# MCU.net
KiCad netlist of a schematic drawn in Altium Designer
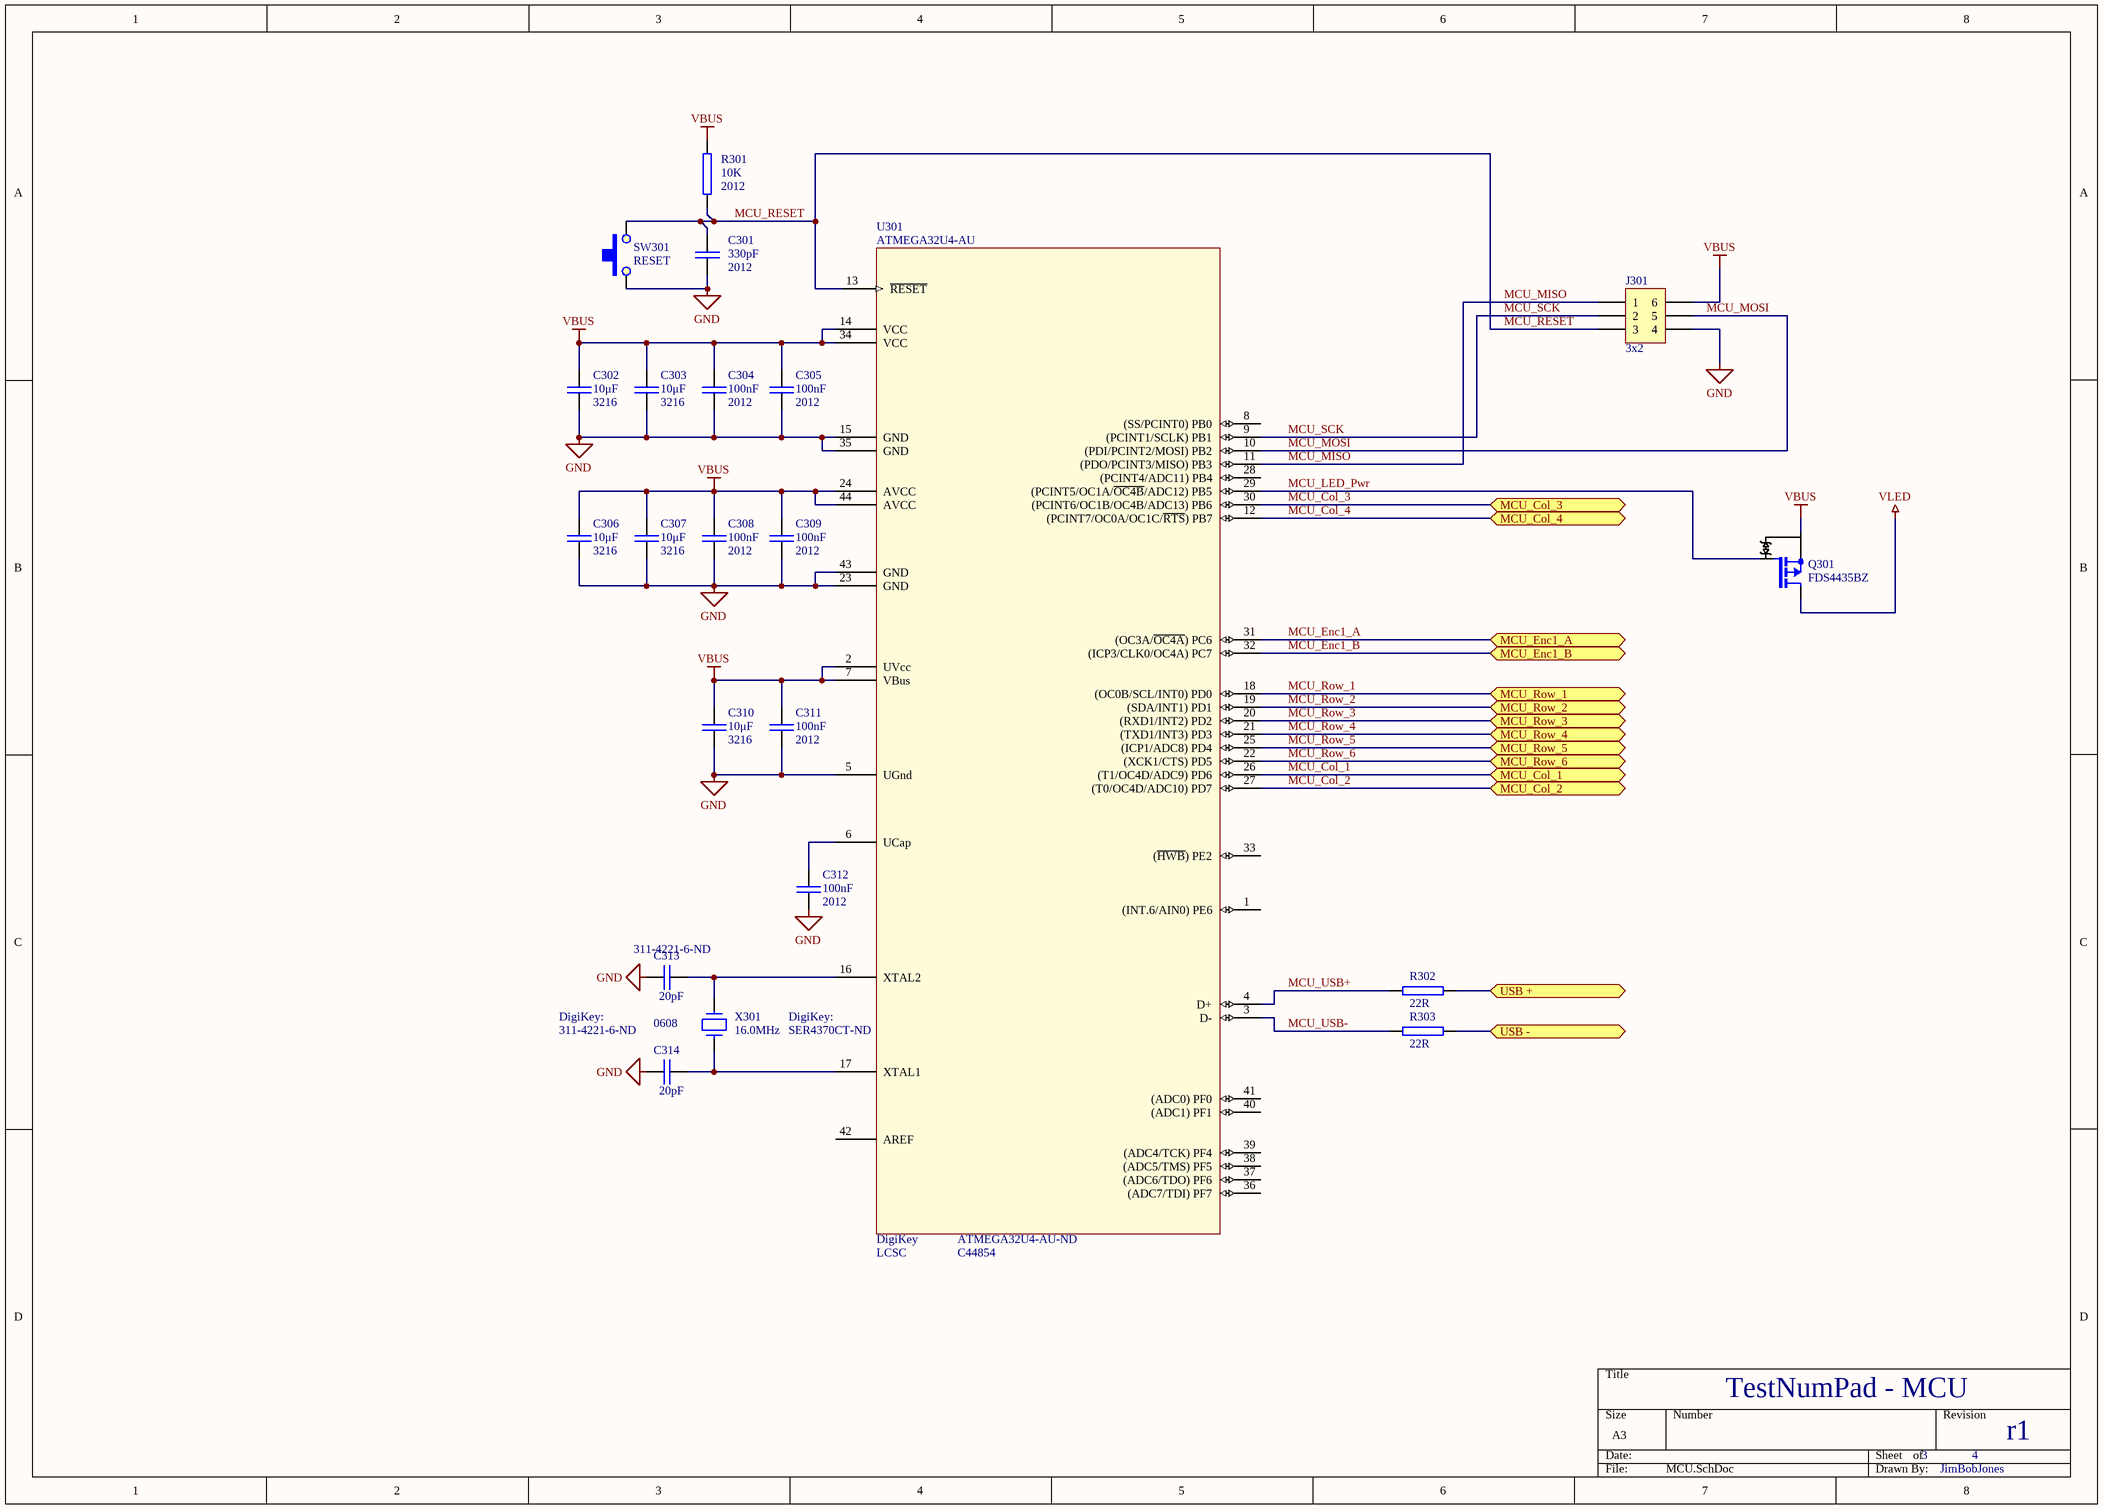
[diagram p0: MCU.SchDoc]

(export (version "E")
  (design (tool "Eeschema 10.0.6"))
  (components
    (comp (ref "C301")
      (value "330pF")
      (footprint "2012C (0805)")
      (description "Capacitor MLCC 50V C0G (NP0) ±10%")
      (libsource (lib "JM_Keyboard") (part "2012C-330pF (NPO)"))
    )
    (comp (ref "C302")
      (value "10μF")
      (footprint "3216C (1206)")
      (description "3216, 25V MLCC X5R CAPACITOR")
      (libsource (lib "JM_Keyboard") (part "3216C-10uF"))
    )
    (comp (ref "C303")
      (value "10μF")
      (footprint "3216C (1206)")
      (description "3216, 25V MLCC X5R CAPACITOR")
      (libsource (lib "JM_Keyboard") (part "3216C-10uF"))
    )
    (comp (ref "C304")
      (value "100nF")
      (footprint "2012C (0805)")
      (description "2012 100nF MLCC Capacitor 50V X7R")
      (libsource (lib "JM_Keyboard") (part "2012C-100nF"))
    )
    (comp (ref "C305")
      (value "100nF")
      (footprint "2012C (0805)")
      (description "2012 100nF MLCC Capacitor 50V X7R")
      (libsource (lib "JM_Keyboard") (part "2012C-100nF"))
    )
    (comp (ref "C306")
      (value "10μF")
      (footprint "3216C (1206)")
      (description "3216, 25V MLCC X5R CAPACITOR")
      (libsource (lib "JM_Keyboard") (part "3216C-10uF"))
    )
    (comp (ref "C307")
      (value "10μF")
      (footprint "3216C (1206)")
      (description "3216, 25V MLCC X5R CAPACITOR")
      (libsource (lib "JM_Keyboard") (part "3216C-10uF"))
    )
    (comp (ref "C308")
      (value "100nF")
      (footprint "2012C (0805)")
      (description "2012 100nF MLCC Capacitor 50V X7R")
      (libsource (lib "JM_Keyboard") (part "2012C-100nF"))
    )
    (comp (ref "C309")
      (value "100nF")
      (footprint "2012C (0805)")
      (description "2012 100nF MLCC Capacitor 50V X7R")
      (libsource (lib "JM_Keyboard") (part "2012C-100nF"))
    )
    (comp (ref "C310")
      (value "10μF")
      (footprint "3216C (1206)")
      (description "3216, 25V MLCC X5R CAPACITOR")
      (libsource (lib "JM_Keyboard") (part "3216C-10uF"))
    )
    (comp (ref "C311")
      (value "100nF")
      (footprint "2012C (0805)")
      (description "2012 100nF MLCC Capacitor 50V X7R")
      (libsource (lib "JM_Keyboard") (part "2012C-100nF"))
    )
    (comp (ref "C312")
      (value "100nF")
      (footprint "2012C (0805)")
      (description "2012 100nF MLCC Capacitor 50V X7R")
      (libsource (lib "JM_Keyboard") (part "2012C-100nF"))
    )
    (comp (ref "C313")
      (value "20pF")
      (footprint "1608C (0603)")
      (description "Capacitor MLCC 50V C0G (NP0) ±10%")
      (fields (field (name "SUPPLIER PART NUMBER 1") "311-4221-6-ND"))
      (libsource (lib "JM_Keyboard") (part "1608C-20pF (NPO)"))
    )
    (comp (ref "C314")
      (value "20pF")
      (footprint "1608C (0603)")
      (description "Capacitor MLCC 50V C0G (NP0) ±10%")
      (fields (field (name "SUPPLIER PART NUMBER 1") "311-4221-6-ND"))
      (libsource (lib "JM_Keyboard") (part "1608C-20pF (NPO)"))
    )
    (comp (ref "J301")
      (value "3x2")
      (footprint "Header-3x2-NoMod")
      (description "0.1 inch, 3 Pin Receptacle, 2 Row")
      (libsource (lib "JM_Keyboard") (part "Header 3x2"))
    )
    (comp (ref "Q301")
      (value "FDS4435BZ")
      (footprint "SO8-150/200mil-GDS")
      (description "P-channel, 30V, 3.2A, 120-75mOhm Enhancement MOSFET with 3.8Kv ESD Protection")
      (libsource (lib "JM_Keyboard") (part "FDS4435BZ"))
    )
    (comp (ref "R301")
      (value "10K")
      (footprint "2012R-10K")
      (description "RESISTOR 2012 1/4 WATT THIN FILM")
      (libsource (lib "JM_Keyboard") (part "2012R-10K"))
    )
    (comp (ref "R302")
      (value "22R")
      (footprint "2012R-22")
      (description "RESISTOR 2012 1/4 WATT THIN FILM")
      (libsource (lib "JM_Keyboard") (part "2012R-22"))
    )
    (comp (ref "R303")
      (value "22R")
      (footprint "2012R-22")
      (description "RESISTOR 2012 1/4 WATT THIN FILM")
      (libsource (lib "JM_Keyboard") (part "2012R-22"))
    )
    (comp (ref "SW301")
      (value "RESET")
      (footprint "SW_PB6x6")
      (description "6mm, SPST Tact switch (DPST Only 1 Contact Used)")
      (libsource (lib "JM_Keyboard") (part "SWITCH_SPST_PUSH-6mm"))
    )
    (comp (ref "U301")
      (value "ATMEGA32U4-AU")
      (footprint "TQFP-44-0.8")
      (fields
        (field (name "SUPPLIER PART NUMBER 1") "C44854")
        (field (name "SUPPLIER PART NUMBER 2") "ATMEGA32U4-AU-ND")
      )
      (libsource (lib "JM_Keyboard") (part "ATMEGA32U4-AU"))
    )
    (comp (ref "X301")
      (value "16.0MHz")
      (footprint "Crystal_4-SMD")
      (description "16MHz Crystal, 16pF, 60R ESR")
      (fields (field (name "SUPPLIER PART NUMBER 1") "SER4370CT-ND"))
      (libsource (lib "JM_Keyboard") (part "Crystal-16M"))
    )
  )
  (nets
    (net (code "1") (name "/MCU_Col_1") (class "Default")
      (node (ref "U301") (pin "26") (pinfunction "(T1/OC4D/ADC9)_PD6_26") (pintype "bidirectional"))
    )
    (net (code "2") (name "/MCU_Col_2") (class "Default")
      (node (ref "U301") (pin "27") (pinfunction "(T0/OC4D/ADC10)_PD7_27") (pintype "bidirectional"))
    )
    (net (code "3") (name "/MCU_Col_3") (class "Default")
      (node (ref "U301") (pin "30") (pinfunction "(PCINT6/OC1B/OC4B/ADC13)_PB6_30") (pintype "bidirectional"))
    )
    (net (code "4") (name "/MCU_Col_4") (class "Default")
      (node (ref "U301") (pin "12") (pinfunction "(PCINT7/OC0A/OC1C/~{RTS})_PB7_12") (pintype "bidirectional"))
    )
    (net (code "5") (name "/MCU_Enc1_A") (class "Default")
      (node (ref "U301") (pin "31") (pinfunction "(OC3A/~{OC4A})_PC6_31") (pintype "bidirectional"))
    )
    (net (code "6") (name "/MCU_Enc1_B") (class "Default")
      (node (ref "U301") (pin "32") (pinfunction "(ICP3/CLK0/OC4A)_PC7_32") (pintype "bidirectional"))
    )
    (net (code "7") (name "/MCU_LED_Pwr") (class "Default")
      (node (ref "Q301") (pin "G") (pinfunction "G_G") (pintype "passive"))
      (node (ref "U301") (pin "29") (pinfunction "(PCINT5/OC1A/~{OC4B}/ADC12)_PB5_29") (pintype "bidirectional"))
    )
    (net (code "8") (name "/MCU_MISO") (class "Default")
      (node (ref "J301") (pin "1") (pinfunction "1_1") (pintype "passive"))
      (node (ref "U301") (pin "11") (pinfunction "(PDO/PCINT3/MISO)_PB3_11") (pintype "bidirectional"))
    )
    (net (code "9") (name "/MCU_MOSI") (class "Default")
      (node (ref "J301") (pin "5") (pinfunction "5_5") (pintype "passive"))
      (node (ref "U301") (pin "10") (pinfunction "(PDI/PCINT2/MOSI)_PB2_10") (pintype "bidirectional"))
    )
    (net (code "10") (name "/MCU_RESET") (class "Default")
      (node (ref "C301") (pin "1") (pintype "passive"))
      (node (ref "J301") (pin "3") (pinfunction "3_3") (pintype "passive"))
      (node (ref "R301") (pin "2") (pintype "passive"))
      (node (ref "SW301") (pin "3") (pinfunction "COM_3") (pintype "passive"))
      (node (ref "U301") (pin "13") (pinfunction "~{RESET}_13") (pintype "input"))
    )
    (net (code "11") (name "/MCU_Row_1") (class "Default")
      (node (ref "U301") (pin "18") (pinfunction "(OC0B/SCL/INT0)_PD0_18") (pintype "bidirectional"))
    )
    (net (code "12") (name "/MCU_Row_2") (class "Default")
      (node (ref "U301") (pin "19") (pinfunction "(SDA/INT1)_PD1_19") (pintype "bidirectional"))
    )
    (net (code "13") (name "/MCU_Row_3") (class "Default")
      (node (ref "U301") (pin "20") (pinfunction "(RXD1/INT2)_PD2_20") (pintype "bidirectional"))
    )
    (net (code "14") (name "/MCU_Row_4") (class "Default")
      (node (ref "U301") (pin "21") (pinfunction "(TXD1/INT3)_PD3_21") (pintype "bidirectional"))
    )
    (net (code "15") (name "/MCU_Row_5") (class "Default")
      (node (ref "U301") (pin "25") (pinfunction "(ICP1/ADC8)_PD4_25") (pintype "bidirectional"))
    )
    (net (code "16") (name "/MCU_Row_6") (class "Default")
      (node (ref "U301") (pin "22") (pinfunction "(XCK1/CTS)_PD5_22") (pintype "bidirectional"))
    )
    (net (code "17") (name "/MCU_SCK") (class "Default")
      (node (ref "J301") (pin "2") (pinfunction "2_2") (pintype "passive"))
      (node (ref "U301") (pin "9") (pinfunction "(PCINT1/SCLK)_PB1_9") (pintype "bidirectional"))
    )
    (net (code "18") (name "/MCU_USB+") (class "Default")
      (node (ref "R302") (pin "1") (pintype "passive"))
      (node (ref "U301") (pin "4") (pinfunction "D+_4") (pintype "bidirectional"))
    )
    (net (code "19") (name "/MCU_USB-") (class "Default")
      (node (ref "R303") (pin "1") (pintype "passive"))
      (node (ref "U301") (pin "3") (pinfunction "D-_3") (pintype "bidirectional"))
    )
    (net (code "20") (name "/USB +") (class "Default") (node (ref "R302") (pin "2") (pintype "passive")))
    (net (code "21") (name "/USB -") (class "Default") (node (ref "R303") (pin "2") (pintype "passive")))
    (net (code "22") (name "GND") (class "Default")
      (node (ref "C301") (pin "2") (pintype "passive"))
      (node (ref "C302") (pin "2") (pintype "passive"))
      (node (ref "C303") (pin "2") (pintype "passive"))
      (node (ref "C304") (pin "2") (pintype "passive"))
      (node (ref "C305") (pin "2") (pintype "passive"))
      (node (ref "C306") (pin "2") (pintype "passive"))
      (node (ref "C307") (pin "2") (pintype "passive"))
      (node (ref "C308") (pin "2") (pintype "passive"))
      (node (ref "C309") (pin "2") (pintype "passive"))
      (node (ref "C310") (pin "2") (pintype "passive"))
      (node (ref "C311") (pin "2") (pintype "passive"))
      (node (ref "C312") (pin "2") (pintype "passive"))
      (node (ref "C313") (pin "1") (pintype "passive"))
      (node (ref "C314") (pin "1") (pintype "passive"))
      (node (ref "J301") (pin "4") (pinfunction "4_4") (pintype "passive"))
      (node (ref "SW301") (pin "1") (pinfunction "COM_1") (pintype "passive"))
      (node (ref "U301") (pin "15") (pinfunction "GND_15") (pintype "power_in"))
      (node (ref "U301") (pin "23") (pinfunction "GND_23") (pintype "passive"))
      (node (ref "U301") (pin "35") (pinfunction "GND_35") (pintype "power_in"))
      (node (ref "U301") (pin "43") (pinfunction "GND_43") (pintype "power_in"))
      (node (ref "U301") (pin "5") (pinfunction "UGnd_5") (pintype "power_in"))
    )
    (net (code "23") (name "Net-(U301-UCap)") (class "Default")
      (node (ref "C312") (pin "1") (pintype "passive"))
      (node (ref "U301") (pin "6") (pinfunction "UCap_6") (pintype "power_in"))
    )
    (net (code "24") (name "Net-(U301-XTAL1)") (class "Default")
      (node (ref "C314") (pin "2") (pintype "passive"))
      (node (ref "U301") (pin "17") (pinfunction "XTAL1_17") (pintype "passive"))
      (node (ref "X301") (pin "1") (pinfunction "1_1") (pintype "passive"))
    )
    (net (code "25") (name "Net-(U301-XTAL2)") (class "Default")
      (node (ref "C313") (pin "2") (pintype "passive"))
      (node (ref "U301") (pin "16") (pinfunction "XTAL2_16") (pintype "passive"))
      (node (ref "X301") (pin "3") (pinfunction "3_3") (pintype "passive"))
    )
    (net (code "26") (name "VBUS") (class "Default")
      (node (ref "C302") (pin "1") (pintype "passive"))
      (node (ref "C303") (pin "1") (pintype "passive"))
      (node (ref "C304") (pin "1") (pintype "passive"))
      (node (ref "C305") (pin "1") (pintype "passive"))
      (node (ref "C306") (pin "1") (pintype "passive"))
      (node (ref "C307") (pin "1") (pintype "passive"))
      (node (ref "C308") (pin "1") (pintype "passive"))
      (node (ref "C309") (pin "1") (pintype "passive"))
      (node (ref "C310") (pin "1") (pintype "passive"))
      (node (ref "C311") (pin "1") (pintype "passive"))
      (node (ref "J301") (pin "6") (pinfunction "6_6") (pintype "passive"))
      (node (ref "Q301") (pin "S") (pinfunction "S_S") (pintype "passive"))
      (node (ref "R301") (pin "1") (pintype "passive"))
      (node (ref "U301") (pin "14") (pinfunction "VCC_14") (pintype "power_in"))
      (node (ref "U301") (pin "2") (pinfunction "UVcc_2") (pintype "power_in"))
      (node (ref "U301") (pin "24") (pinfunction "AVCC_24") (pintype "passive"))
      (node (ref "U301") (pin "34") (pinfunction "VCC_34") (pintype "power_in"))
      (node (ref "U301") (pin "44") (pinfunction "AVCC_44") (pintype "power_in"))
      (node (ref "U301") (pin "7") (pinfunction "VBus_7") (pintype "power_in"))
    )
    (net (code "27") (name "VLED") (class "Default")
      (node (ref "Q301") (pin "D") (pinfunction "D_D") (pintype "passive"))
    )
    (net (code "28") (name "unconnected-(U301-(ADC0)_PF0-Pad41)") (class "Default")
      (node (ref "U301") (pin "41") (pinfunction "(ADC0)_PF0_41") (pintype "bidirectional"))
    )
    (net (code "29") (name "unconnected-(U301-(ADC1)_PF1-Pad40)") (class "Default")
      (node (ref "U301") (pin "40") (pinfunction "(ADC1)_PF1_40") (pintype "bidirectional"))
    )
    (net (code "30") (name "unconnected-(U301-(ADC4{slash}TCK)_PF4-Pad39)") (class "Default")
      (node (ref "U301") (pin "39") (pinfunction "(ADC4/TCK)_PF4_39") (pintype "bidirectional"))
    )
    (net (code "31") (name "unconnected-(U301-(ADC5{slash}TMS)_PF5-Pad38)") (class "Default")
      (node (ref "U301") (pin "38") (pinfunction "(ADC5/TMS)_PF5_38") (pintype "bidirectional"))
    )
    (net (code "32") (name "unconnected-(U301-(ADC6{slash}TDO)_PF6-Pad37)") (class "Default")
      (node (ref "U301") (pin "37") (pinfunction "(ADC6/TDO)_PF6_37") (pintype "bidirectional"))
    )
    (net (code "33") (name "unconnected-(U301-(ADC7{slash}TDI)_PF7-Pad36)") (class "Default")
      (node (ref "U301") (pin "36") (pinfunction "(ADC7/TDI)_PF7_36") (pintype "bidirectional"))
    )
    (net (code "34") (name "unconnected-(U301-(INT.6{slash}AIN0)_PE6-Pad1)") (class "Default")
      (node (ref "U301") (pin "1") (pinfunction "(INT.6/AIN0)_PE6_1") (pintype "bidirectional"))
    )
    (net (code "35") (name "unconnected-(U301-(PCINT4{slash}ADC11)_PB4-Pad28)") (class "Default")
      (node (ref "U301") (pin "28") (pinfunction "(PCINT4/ADC11)_PB4_28") (pintype "bidirectional"))
    )
    (net (code "36") (name "unconnected-(U301-(SS{slash}PCINT0)_PB0-Pad8)") (class "Default")
      (node (ref "U301") (pin "8") (pinfunction "(SS/PCINT0)_PB0_8") (pintype "bidirectional"))
    )
    (net (code "37") (name "unconnected-(U301-(~{HWB})_PE2-Pad33)") (class "Default")
      (node (ref "U301") (pin "33") (pinfunction "(~{HWB})_PE2_33") (pintype "bidirectional"))
    )
    (net (code "38") (name "unconnected-(U301-AREF-Pad42)") (class "Default")
      (node (ref "U301") (pin "42") (pinfunction "AREF_42") (pintype "passive"))
    )
  )
)
